# SCH_Iris_OnBoardSystem.net
KiCad netlist of a schematic drawn in EasyEDA
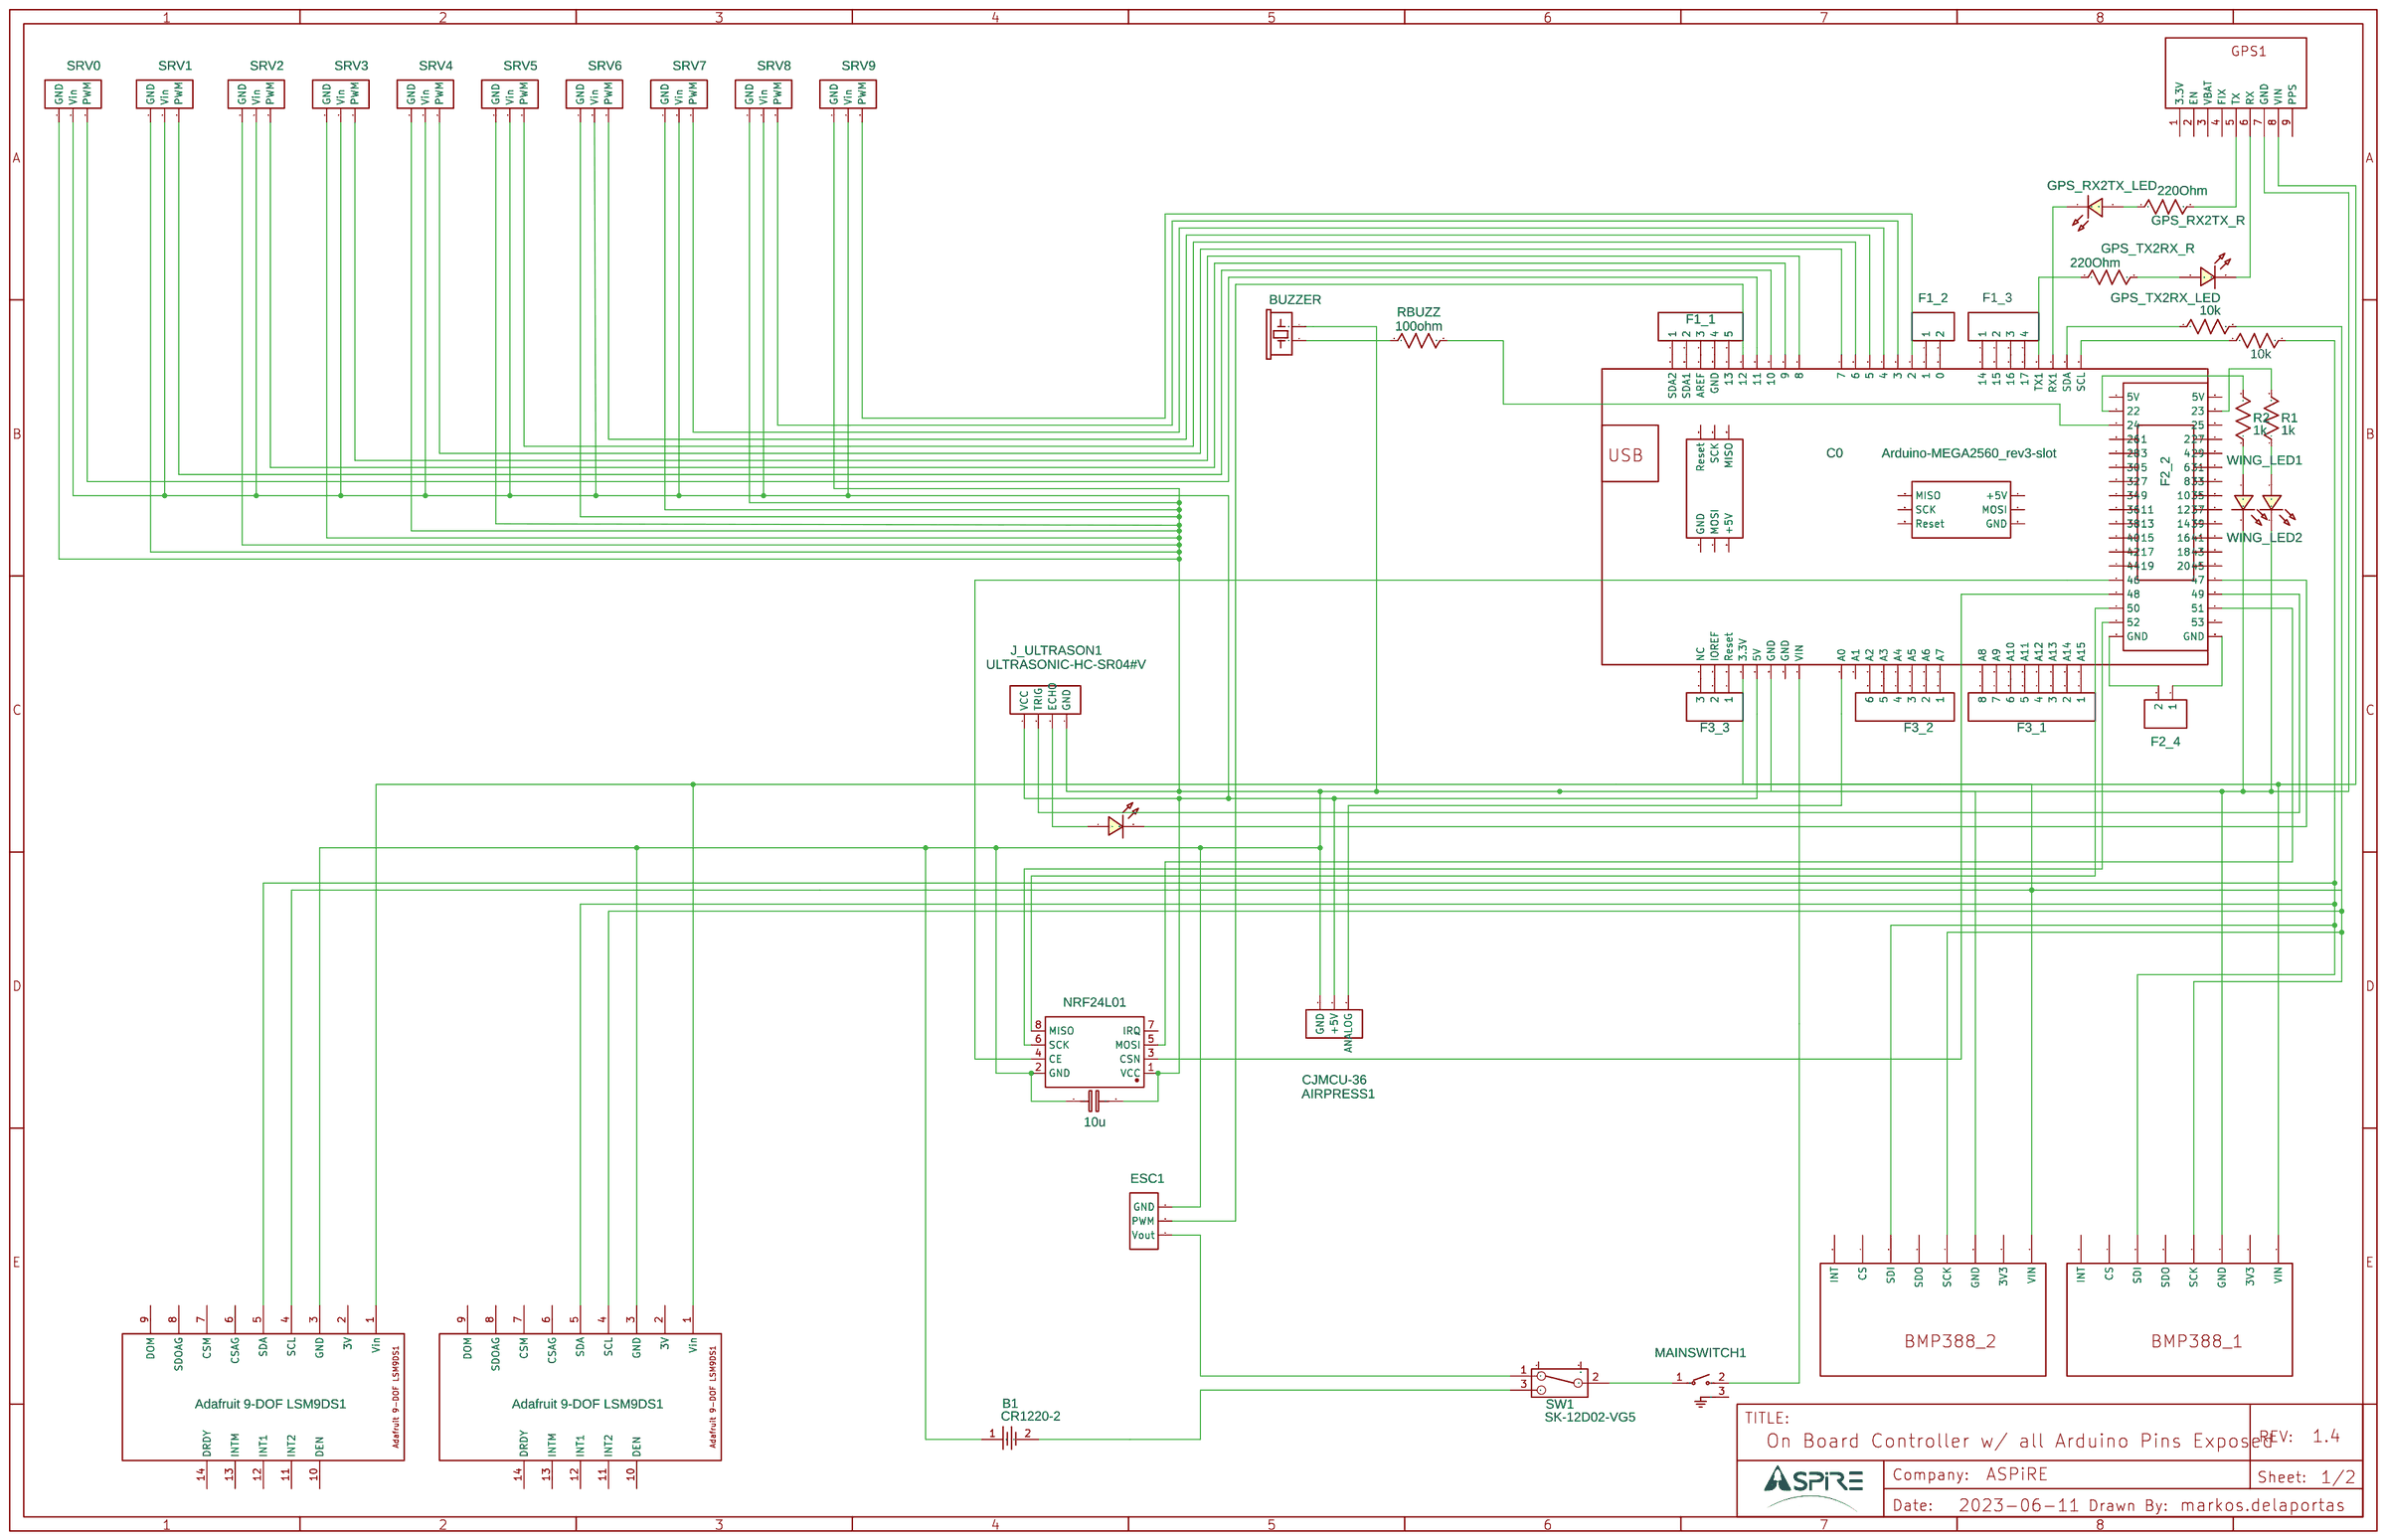
[diagram p0: schematic sheet]

(export (version "E")
  (design (tool "Eeschema 10.0.6"))
  (components
    (comp (ref "AIRPRESS1")
      (value "CJMCU-36")
      (fields (field (name "BOM_Supplier Part") "C180248"))
      (libsource (lib "") (part "HDR-M-2.54_1x3_1"))
    )
    (comp (ref "B1")
      (value "CR1220-2")
      (fields (field (name "BOM_Supplier Part") "C70381"))
      (libsource (lib "") (part "CR1220-2"))
    )
    (comp (ref "BUZZER") (value "BUZZER-PTH_NO_SILK") (libsource (lib "") (part "BUZZER-PTH_NO_SILK")))
    (comp (ref "C0")
      (value "Arduino-MEGA2560_rev3-slot")
      (libsource (lib "") (part "Arduino-MEGA2560_rev3-slot"))
    )
    (comp (ref "C1_2") (value "10u") (libsource (lib "") (part "C_RAD-0.1_EU")))
    (comp (ref "ESC1")
      (value "ESC")
      (fields (field (name "BOM_Supplier Part") "C180248"))
      (libsource (lib "") (part "HDR-M-2.54_1x3_2"))
    )
    (comp (ref "F1_1")
      (value "HDR-F-2.54_1x5")
      (fields (field (name "BOM_Supplier Part") "C50950"))
      (libsource (lib "") (part "HDR-F-2.54_1x5"))
    )
    (comp (ref "F1_2")
      (value "HDR-F-2.54_1x2")
      (fields (field (name "BOM_Supplier Part") "C49661"))
      (libsource (lib "") (part "HDR-F-2.54_1x2_1"))
    )
    (comp (ref "F1_3")
      (value "HDR-F-2.54_1x4")
      (fields (field (name "BOM_Supplier Part") "C225501"))
      (libsource (lib "") (part "HDR-F-2.54_1x4"))
    )
    (comp (ref "F2_2")
      (value "HDR-F-2.54_2x10")
      (fields (field (name "BOM_Supplier Part") "C30867"))
      (libsource (lib "") (part "HDR-F-2.54_2x10"))
    )
    (comp (ref "F2_4")
      (value "HDR-F-2.54_1x2")
      (fields (field (name "BOM_Supplier Part") "C49661"))
      (libsource (lib "") (part "HDR-F-2.54_1x2"))
    )
    (comp (ref "F3_1")
      (value "HDR-F-2.54_1x8")
      (fields (field (name "BOM_Supplier Part") "C225505"))
      (libsource (lib "") (part "HDR-F-2.54_1x8"))
    )
    (comp (ref "F3_2")
      (value "HDR-F-2.54_1x6")
      (fields (field (name "BOM_Supplier Part") "C40877"))
      (libsource (lib "") (part "HDR-F-2.54_1x6"))
    )
    (comp (ref "F3_3")
      (value "HDR-F-2.54_1x3")
      (fields (field (name "BOM_Supplier Part") "C146690"))
      (libsource (lib "") (part "HDR-F-2.54_1x3"))
    )
    (comp (ref "GPS2")
      (value "ULTIMATE GPS MODULE")
      (fields
        (field (name "BOM_Manufacturer Part") "Solid State Relays")
        (field (name "BOM_Supplier Part") "746")
      )
      (libsource (lib "") (part "ULTIMATE GPS MODULE"))
    )
    (comp (ref "GPS_RX2TX_LED")
      (value "LED-TH-5mm_R")
      (fields
        (field (name "BOM_Manufacturer Part") "333-2SURD/S530-A3")
        (field (name "BOM_Supplier Part") "C87271")
      )
      (libsource (lib "") (part "LED-TH-5mm_R"))
    )
    (comp (ref "GPS_RX2TX_R") (value "220Ohm") (libsource (lib "") (part "R_AXIAL-0.3_US_3")))
    (comp (ref "GPS_TX2RX_LED") (value "LED-TH-5mm_B") (libsource (lib "") (part "LED-TH-5mm_B")))
    (comp (ref "GPS_TX2RX_R") (value "220Ohm") (libsource (lib "") (part "R_AXIAL-0.3_US_1")))
    (comp (ref "J_ULTRASON1")
      (value "ULTRASONIC-HC-SR04#V")
      (fields (field (name "BOM_Supplier Part") "C124378"))
      (libsource (lib "") (part "HDR-M-2.54_1x4"))
    )
    (comp (ref "LED1_2")
      (value "LED-TH-3mm_R")
      (fields
        (field (name "BOM_Manufacturer Part") "204-10SDRD/S530-A3-L")
        (field (name "BOM_Supplier Part") "C84774")
      )
      (libsource (lib "") (part "LED-TH-3mm_R"))
    )
    (comp (ref "MAINSWITCH1")
      (value "GT-TCB73B-H090-L1")
      (fields (field (name "BOM_Supplier Part") "C2890355"))
      (libsource (lib "") (part "GT-TCB73B-H090-L1"))
    )
    (comp (ref "MK2")
      (value "NRF24L01")
      (fields (field (name "BOM_Manufacturer Part") "NF-04") (field (name "BOM_Supplier Part") "C90751"))
      (libsource (lib "") (part "NRF24L01"))
    )
    (comp (ref "R1") (value "1k") (libsource (lib "") (part "R_AXIAL-0.3_US")))
    (comp (ref "R1_2") (value "1k") (libsource (lib "") (part "R_AXIAL-0.4_US")))
    (comp (ref "R2") (value "1k") (libsource (lib "") (part "R_AXIAL-0.3_US")))
    (comp (ref "R2_2") (value "10k") (libsource (lib "") (part "R_AXIAL-0.4_US_1")))
    (comp (ref "RBUZZ") (value "100ohm") (libsource (lib "") (part "R_AXIAL-0.3_US_2")))
    (comp (ref "SRV0")
      (value "HDR-M-2.54_1x3")
      (fields (field (name "BOM_Supplier Part") "C180248"))
      (libsource (lib "") (part "HDR-M-2.54_1x3"))
    )
    (comp (ref "SRV1")
      (value "HDR-M-2.54_1x3")
      (fields (field (name "BOM_Supplier Part") "C180248"))
      (libsource (lib "") (part "HDR-M-2.54_1x3"))
    )
    (comp (ref "SRV2")
      (value "HDR-M-2.54_1x3")
      (fields (field (name "BOM_Supplier Part") "C180248"))
      (libsource (lib "") (part "HDR-M-2.54_1x3"))
    )
    (comp (ref "SRV3")
      (value "HDR-M-2.54_1x3")
      (fields (field (name "BOM_Supplier Part") "C180248"))
      (libsource (lib "") (part "HDR-M-2.54_1x3"))
    )
    (comp (ref "SRV4")
      (value "HDR-M-2.54_1x3")
      (fields (field (name "BOM_Supplier Part") "C180248"))
      (libsource (lib "") (part "HDR-M-2.54_1x3"))
    )
    (comp (ref "SRV5")
      (value "HDR-M-2.54_1x3")
      (fields (field (name "BOM_Supplier Part") "C180248"))
      (libsource (lib "") (part "HDR-M-2.54_1x3"))
    )
    (comp (ref "SRV6")
      (value "HDR-M-2.54_1x3")
      (fields (field (name "BOM_Supplier Part") "C180248"))
      (libsource (lib "") (part "HDR-M-2.54_1x3"))
    )
    (comp (ref "SRV7")
      (value "HDR-M-2.54_1x3")
      (fields (field (name "BOM_Supplier Part") "C180248"))
      (libsource (lib "") (part "HDR-M-2.54_1x3"))
    )
    (comp (ref "SRV8")
      (value "HDR-M-2.54_1x3")
      (fields (field (name "BOM_Supplier Part") "C180248"))
      (libsource (lib "") (part "HDR-M-2.54_1x3"))
    )
    (comp (ref "SRV9")
      (value "HDR-M-2.54_1x3")
      (fields (field (name "BOM_Supplier Part") "C180248"))
      (libsource (lib "") (part "HDR-M-2.54_1x3"))
    )
    (comp (ref "SW1")
      (value "SK-12D02-VG5")
      (fields (field (name "BOM_Supplier Part") "C136722"))
      (libsource (lib "") (part "SK-12D02-VG5"))
    )
    (comp (ref "U2")
      (value "Adafruit 9-DOF LSM9DS1")
      (fields (field (name "BOM_Manufacturer Part") "4634") (field (name "BOM_Supplier Part") "ADA4634"))
      (libsource (lib "") (part "Adafruit 9-DOF LSM9DS1"))
    )
    (comp (ref "U3")
      (value "Adafruit 9-DOF LSM9DS1")
      (fields (field (name "BOM_Manufacturer Part") "4634") (field (name "BOM_Supplier Part") "ADA4634"))
      (libsource (lib "") (part "Adafruit 9-DOF LSM9DS1"))
    )
    (comp (ref "U6")
      (value "ADAFRUIT_BMP388_2")
      (fields (field (name "BOM_Manufacturer Part") "BMP388") (field (name "BOM_Supplier Part") "3966"))
      (libsource (lib "") (part "ADAFRUIT BMP388 BOARD COPY"))
    )
    (comp (ref "U7")
      (value "ADAFRUIT_BMP388_1")
      (fields (field (name "BOM_Manufacturer Part") "BMP388") (field (name "BOM_Supplier Part") "3966"))
      (libsource (lib "") (part "ADAFRUIT BMP388 BOARD COPY_1"))
    )
    (comp (ref "WING_LED1")
      (value "LED-TH-5mm_G")
      (fields
        (field (name "BOM_Manufacturer Part") "333-2SYGD/S530-E2")
        (field (name "BOM_Supplier Part") "C88163")
      )
      (libsource (lib "") (part "LED-TH-5mm_G"))
    )
    (comp (ref "WING_LED2")
      (value "LED-TH-5mm_G")
      (fields
        (field (name "BOM_Manufacturer Part") "333-2SYGD/S530-E2")
        (field (name "BOM_Supplier Part") "C88163")
      )
      (libsource (lib "") (part "LED-TH-5mm_G"))
    )
  )
  (nets
    (net (code "1") (name "Net-(AIRPRESS1-+5V)") (class "Default")
      (node (ref "AIRPRESS1") (pin "2") (pinfunction "+5V_2") (pintype "input"))
      (node (ref "C0") (pin "5V") (pinfunction "5V_5V") (pintype "unspecified"))
      (node (ref "C1_2") (pin "2") (pinfunction "2_2") (pintype "unspecified"))
      (node (ref "J_ULTRASON1") (pin "1") (pinfunction "VCC_1") (pintype "unspecified"))
      (node (ref "MK2") (pin "1") (pinfunction "VCC_1") (pintype "unspecified"))
      (node (ref "SRV0") (pin "2") (pinfunction "Vin_2") (pintype "input"))
      (node (ref "SRV1") (pin "2") (pinfunction "Vin_2") (pintype "input"))
      (node (ref "SRV2") (pin "2") (pinfunction "Vin_2") (pintype "input"))
      (node (ref "SRV3") (pin "2") (pinfunction "Vin_2") (pintype "input"))
      (node (ref "SRV4") (pin "2") (pinfunction "Vin_2") (pintype "input"))
      (node (ref "SRV5") (pin "2") (pinfunction "Vin_2") (pintype "input"))
      (node (ref "SRV6") (pin "2") (pinfunction "Vin_2") (pintype "input"))
      (node (ref "SRV7") (pin "2") (pinfunction "Vin_2") (pintype "input"))
      (node (ref "SRV8") (pin "2") (pinfunction "Vin_2") (pintype "input"))
      (node (ref "SRV9") (pin "2") (pinfunction "Vin_2") (pintype "input"))
    )
    (net (code "2") (name "Net-(AIRPRESS1-ANALOG)") (class "Default")
      (node (ref "AIRPRESS1") (pin "1") (pinfunction "ANALOG_1") (pintype "input"))
      (node (ref "C0") (pin "A0") (pinfunction "A0_A0") (pintype "unspecified"))
    )
    (net (code "3") (name "Net-(AIRPRESS1-GND)") (class "Default")
      (node (ref "AIRPRESS1") (pin "3") (pinfunction "GND_3") (pintype "input"))
      (node (ref "B1") (pin "1") (pinfunction "1_1") (pintype "input"))
      (node (ref "BUZZER") (pin "-") (pinfunction "2_-") (pintype "bidirectional"))
      (node (ref "C1_2") (pin "1") (pinfunction "1_1") (pintype "unspecified"))
      (node (ref "ESC1") (pin "3") (pinfunction "GND_3") (pintype "input"))
      (node (ref "GPS2") (pin "7") (pinfunction "GND_7") (pintype "unspecified"))
      (node (ref "J_ULTRASON1") (pin "4") (pinfunction "GND_4") (pintype "unspecified"))
      (node (ref "MK2") (pin "2") (pinfunction "GND_2") (pintype "unspecified"))
      (node (ref "SRV0") (pin "1") (pinfunction "GND_1") (pintype "input"))
      (node (ref "SRV1") (pin "1") (pinfunction "GND_1") (pintype "input"))
      (node (ref "SRV2") (pin "1") (pinfunction "GND_1") (pintype "input"))
      (node (ref "SRV3") (pin "1") (pinfunction "GND_1") (pintype "input"))
      (node (ref "SRV4") (pin "1") (pinfunction "GND_1") (pintype "input"))
      (node (ref "SRV5") (pin "1") (pinfunction "GND_1") (pintype "input"))
      (node (ref "SRV6") (pin "1") (pinfunction "GND_1") (pintype "input"))
      (node (ref "SRV7") (pin "1") (pinfunction "GND_1") (pintype "input"))
      (node (ref "SRV8") (pin "1") (pinfunction "GND_1") (pintype "input"))
      (node (ref "SRV9") (pin "1") (pinfunction "GND_1") (pintype "input"))
      (node (ref "U2") (pin "3") (pinfunction "GND_3") (pintype "unspecified"))
      (node (ref "U3") (pin "3") (pinfunction "GND_3") (pintype "unspecified"))
      (node (ref "U7") (pin "3") (pinfunction "GND_3") (pintype "passive"))
      (node (ref "WING_LED1") (pin "2") (pinfunction "2_2") (pintype "unspecified"))
      (node (ref "WING_LED2") (pin "2") (pinfunction "2_2") (pintype "unspecified"))
    )
    (net (code "4") (name "Net-(B1-Pad2)") (class "Default")
      (node (ref "B1") (pin "2") (pinfunction "2_2") (pintype "input"))
      (node (ref "SW1") (pin "3") (pinfunction "3_3") (pintype "unspecified"))
    )
    (net (code "5") (name "Net-(BUZZER-1)") (class "Default")
      (node (ref "BUZZER") (pin "+") (pinfunction "1_+") (pintype "bidirectional"))
      (node (ref "RBUZZ") (pin "1") (pinfunction "1_1") (pintype "unspecified"))
    )
    (net (code "6") (name "Net-(C0-GND-PadGND...)") (class "Default")
      (node (ref "C0") (pin "GND...") (pinfunction "GND_GND...") (pintype "input"))
      (node (ref "F2_4") (pin "2") (pinfunction "2_2") (pintype "input"))
    )
    (net (code "7") (name "Net-(C0-GND-PadGND....)") (class "Default")
      (node (ref "C0") (pin "GND....") (pinfunction "GND_GND....") (pintype "input"))
      (node (ref "F2_4") (pin "1") (pinfunction "1_1") (pintype "input"))
    )
    (net (code "8") (name "Net-(C0-GND-PadGND.....)") (class "Default")
      (node (ref "C0") (pin "GND.....") (pinfunction "GND_GND.....") (pintype "unspecified"))
      (node (ref "F1_1") (pin "4") (pinfunction "4_4") (pintype "unspecified"))
    )
    (net (code "9") (name "Net-(C0-NC)") (class "Default")
      (node (ref "C0") (pin "87") (pinfunction "NC_87") (pintype "unspecified"))
      (node (ref "F3_3") (pin "3") (pinfunction "3_3") (pintype "input"))
    )
    (net (code "10") (name "Net-(C0-Pad0)") (class "Default")
      (node (ref "C0") (pin "0") (pinfunction "0_0") (pintype "unspecified"))
      (node (ref "F1_2") (pin "2") (pinfunction "2_2") (pintype "input"))
    )
    (net (code "11") (name "Net-(C0-Pad1)") (class "Default")
      (node (ref "C0") (pin "1") (pinfunction "1_1") (pintype "unspecified"))
      (node (ref "F1_2") (pin "1") (pinfunction "1_1") (pintype "input"))
    )
    (net (code "12") (name "Net-(C0-Pad13)") (class "Default")
      (node (ref "C0") (pin "13") (pinfunction "13_13") (pintype "unspecified"))
      (node (ref "F1_1") (pin "5") (pinfunction "5_5") (pintype "unspecified"))
    )
    (net (code "13") (name "Net-(C0-Pad14)") (class "Default")
      (node (ref "C0") (pin "14") (pinfunction "14_14") (pintype "unspecified"))
      (node (ref "F1_3") (pin "1") (pinfunction "1_1") (pintype "unspecified"))
    )
    (net (code "14") (name "Net-(C0-Pad15)") (class "Default")
      (node (ref "C0") (pin "15") (pinfunction "15_15") (pintype "unspecified"))
      (node (ref "F1_3") (pin "2") (pinfunction "2_2") (pintype "unspecified"))
    )
    (net (code "15") (name "Net-(C0-Pad16)") (class "Default")
      (node (ref "C0") (pin "16") (pinfunction "16_16") (pintype "unspecified"))
      (node (ref "F1_3") (pin "3") (pinfunction "3_3") (pintype "unspecified"))
    )
    (net (code "16") (name "Net-(C0-Pad17)") (class "Default")
      (node (ref "C0") (pin "17") (pinfunction "17_17") (pintype "unspecified"))
      (node (ref "F1_3") (pin "4") (pinfunction "4_4") (pintype "unspecified"))
    )
    (net (code "17") (name "Net-(C0-Pad22)") (class "Default")
      (node (ref "C0") (pin "22") (pinfunction "22_22") (pintype "input"))
      (node (ref "R2") (pin "2") (pinfunction "2_2") (pintype "unspecified"))
    )
    (net (code "18") (name "Net-(C0-Pad23)") (class "Default")
      (node (ref "C0") (pin "23") (pinfunction "23_23") (pintype "input"))
      (node (ref "R1") (pin "2") (pinfunction "2_2") (pintype "unspecified"))
    )
    (net (code "19") (name "Net-(C0-Pad24)") (class "Default")
      (node (ref "C0") (pin "24") (pinfunction "24_24") (pintype "input"))
      (node (ref "RBUZZ") (pin "2") (pinfunction "2_2") (pintype "unspecified"))
    )
    (net (code "20") (name "Net-(C0-Pad26)") (class "Default")
      (node (ref "C0") (pin "26") (pinfunction "26_26") (pintype "input"))
      (node (ref "F2_2") (pin "1") (pinfunction "1_1") (pintype "input"))
    )
    (net (code "21") (name "Net-(C0-Pad27)") (class "Default")
      (node (ref "C0") (pin "27") (pinfunction "27_27") (pintype "input"))
      (node (ref "F2_2") (pin "2") (pinfunction "2_2") (pintype "input"))
    )
    (net (code "22") (name "Net-(C0-Pad28)") (class "Default")
      (node (ref "C0") (pin "28") (pinfunction "28_28") (pintype "input"))
      (node (ref "F2_2") (pin "3") (pinfunction "3_3") (pintype "input"))
    )
    (net (code "23") (name "Net-(C0-Pad29)") (class "Default")
      (node (ref "C0") (pin "29") (pinfunction "29_29") (pintype "input"))
      (node (ref "F2_2") (pin "4") (pinfunction "4_4") (pintype "input"))
    )
    (net (code "24") (name "Net-(C0-Pad30)") (class "Default")
      (node (ref "C0") (pin "30") (pinfunction "30_30") (pintype "input"))
      (node (ref "F2_2") (pin "5") (pinfunction "5_5") (pintype "input"))
    )
    (net (code "25") (name "Net-(C0-Pad31)") (class "Default")
      (node (ref "C0") (pin "31") (pinfunction "31_31") (pintype "input"))
      (node (ref "F2_2") (pin "6") (pinfunction "6_6") (pintype "input"))
    )
    (net (code "26") (name "Net-(C0-Pad32)") (class "Default")
      (node (ref "C0") (pin "32") (pinfunction "32_32") (pintype "input"))
      (node (ref "F2_2") (pin "7") (pinfunction "7_7") (pintype "input"))
    )
    (net (code "27") (name "Net-(C0-Pad33)") (class "Default")
      (node (ref "C0") (pin "33") (pinfunction "33_33") (pintype "input"))
      (node (ref "F2_2") (pin "8") (pinfunction "8_8") (pintype "input"))
    )
    (net (code "28") (name "Net-(C0-Pad34)") (class "Default")
      (node (ref "C0") (pin "34") (pinfunction "34_34") (pintype "input"))
      (node (ref "F2_2") (pin "9") (pinfunction "9_9") (pintype "input"))
    )
    (net (code "29") (name "Net-(C0-Pad35)") (class "Default")
      (node (ref "C0") (pin "35") (pinfunction "35_35") (pintype "input"))
      (node (ref "F2_2") (pin "10") (pinfunction "10_10") (pintype "input"))
    )
    (net (code "30") (name "Net-(C0-Pad36)") (class "Default")
      (node (ref "C0") (pin "36") (pinfunction "36_36") (pintype "input"))
      (node (ref "F2_2") (pin "11") (pinfunction "11_11") (pintype "input"))
    )
    (net (code "31") (name "Net-(C0-Pad37)") (class "Default")
      (node (ref "C0") (pin "37") (pinfunction "37_37") (pintype "input"))
      (node (ref "F2_2") (pin "12") (pinfunction "12_12") (pintype "input"))
    )
    (net (code "32") (name "Net-(C0-Pad38)") (class "Default")
      (node (ref "C0") (pin "38") (pinfunction "38_38") (pintype "input"))
      (node (ref "F2_2") (pin "13") (pinfunction "13_13") (pintype "input"))
    )
    (net (code "33") (name "Net-(C0-Pad39)") (class "Default")
      (node (ref "C0") (pin "39") (pinfunction "39_39") (pintype "input"))
      (node (ref "F2_2") (pin "14") (pinfunction "14_14") (pintype "input"))
    )
    (net (code "34") (name "Net-(C0-Pad40)") (class "Default")
      (node (ref "C0") (pin "40") (pinfunction "40_40") (pintype "input"))
      (node (ref "F2_2") (pin "15") (pinfunction "15_15") (pintype "input"))
    )
    (net (code "35") (name "Net-(C0-Pad41)") (class "Default")
      (node (ref "C0") (pin "41") (pinfunction "41_41") (pintype "input"))
      (node (ref "F2_2") (pin "16") (pinfunction "16_16") (pintype "input"))
    )
    (net (code "36") (name "Net-(C0-Pad42)") (class "Default")
      (node (ref "C0") (pin "42") (pinfunction "42_42") (pintype "input"))
      (node (ref "F2_2") (pin "17") (pinfunction "17_17") (pintype "input"))
    )
    (net (code "37") (name "Net-(C0-Pad43)") (class "Default")
      (node (ref "C0") (pin "43") (pinfunction "43_43") (pintype "input"))
      (node (ref "F2_2") (pin "18") (pinfunction "18_18") (pintype "input"))
    )
    (net (code "38") (name "Net-(C0-Pad44)") (class "Default")
      (node (ref "C0") (pin "44") (pinfunction "44_44") (pintype "input"))
      (node (ref "F2_2") (pin "19") (pinfunction "19_19") (pintype "input"))
    )
    (net (code "39") (name "Net-(C0-Pad45)") (class "Default")
      (node (ref "C0") (pin "45") (pinfunction "45_45") (pintype "input"))
      (node (ref "F2_2") (pin "20") (pinfunction "20_20") (pintype "input"))
    )
    (net (code "40") (name "Net-(C0-Pad47)") (class "Default")
      (node (ref "C0") (pin "47") (pinfunction "47_47") (pintype "input"))
      (node (ref "LED1_2") (pin "2") (pinfunction "2_2") (pintype "unspecified"))
    )
    (net (code "41") (name "Net-(C0-PadA2)") (class "Default")
      (node (ref "C0") (pin "A2") (pinfunction "A2_A2") (pintype "unspecified"))
      (node (ref "F3_2") (pin "6") (pinfunction "6_6") (pintype "input"))
    )
    (net (code "42") (name "Net-(C0-PadA3)") (class "Default")
      (node (ref "C0") (pin "A3") (pinfunction "A3_A3") (pintype "unspecified"))
      (node (ref "F3_2") (pin "5") (pinfunction "5_5") (pintype "input"))
    )
    (net (code "43") (name "Net-(C0-PadA4)") (class "Default")
      (node (ref "C0") (pin "A4") (pinfunction "A4_A4") (pintype "unspecified"))
      (node (ref "F3_2") (pin "4") (pinfunction "4_4") (pintype "input"))
    )
    (net (code "44") (name "Net-(C0-PadA5)") (class "Default")
      (node (ref "C0") (pin "A5") (pinfunction "A5_A5") (pintype "unspecified"))
      (node (ref "F3_2") (pin "3") (pinfunction "3_3") (pintype "input"))
    )
    (net (code "45") (name "Net-(C0-PadA6)") (class "Default")
      (node (ref "C0") (pin "A6") (pinfunction "A6_A6") (pintype "unspecified"))
      (node (ref "F3_2") (pin "2") (pinfunction "2_2") (pintype "input"))
    )
    (net (code "46") (name "Net-(C0-PadA7)") (class "Default")
      (node (ref "C0") (pin "A7") (pinfunction "A7_A7") (pintype "unspecified"))
      (node (ref "F3_2") (pin "1") (pinfunction "1_1") (pintype "input"))
    )
    (net (code "47") (name "Net-(C0-PadA8)") (class "Default")
      (node (ref "C0") (pin "A8") (pinfunction "A8_A8") (pintype "unspecified"))
      (node (ref "F3_1") (pin "8") (pinfunction "8_8") (pintype "unspecified"))
    )
    (net (code "48") (name "Net-(C0-PadA9)") (class "Default")
      (node (ref "C0") (pin "A9") (pinfunction "A9_A9") (pintype "unspecified"))
      (node (ref "F3_1") (pin "7") (pinfunction "7_7") (pintype "unspecified"))
    )
    (net (code "49") (name "Net-(C0-PadA10)") (class "Default")
      (node (ref "C0") (pin "A10") (pinfunction "A10_A10") (pintype "unspecified"))
      (node (ref "F3_1") (pin "6") (pinfunction "6_6") (pintype "unspecified"))
    )
    (net (code "50") (name "Net-(C0-PadA11)") (class "Default")
      (node (ref "C0") (pin "A11") (pinfunction "A11_A11") (pintype "unspecified"))
      (node (ref "F3_1") (pin "5") (pinfunction "5_5") (pintype "unspecified"))
    )
    (net (code "51") (name "Net-(C0-PadA12)") (class "Default")
      (node (ref "C0") (pin "A12") (pinfunction "A12_A12") (pintype "unspecified"))
      (node (ref "F3_1") (pin "4") (pinfunction "4_4") (pintype "unspecified"))
    )
    (net (code "52") (name "Net-(C0-PadA13)") (class "Default")
      (node (ref "C0") (pin "A13") (pinfunction "A13_A13") (pintype "unspecified"))
      (node (ref "F3_1") (pin "3") (pinfunction "3_3") (pintype "unspecified"))
    )
    (net (code "53") (name "Net-(C0-PadA14)") (class "Default")
      (node (ref "C0") (pin "A14") (pinfunction "A14_A14") (pintype "unspecified"))
      (node (ref "F3_1") (pin "2") (pinfunction "2_2") (pintype "unspecified"))
    )
    (net (code "54") (name "Net-(C0-PadA15)") (class "Default")
      (node (ref "C0") (pin "A15") (pinfunction "A15_A15") (pintype "unspecified"))
      (node (ref "F3_1") (pin "1") (pinfunction "1_1") (pintype "unspecified"))
    )
    (net (code "55") (name "Net-(C0-PadAREF)") (class "Default")
      (node (ref "C0") (pin "AREF") (pinfunction "AREF_AREF") (pintype "unspecified"))
      (node (ref "F1_1") (pin "3") (pinfunction "3_3") (pintype "unspecified"))
    )
    (net (code "56") (name "Net-(C0-PadIOREF)") (class "Default")
      (node (ref "C0") (pin "IOREF") (pinfunction "IOREF_IOREF") (pintype "unspecified"))
      (node (ref "F3_3") (pin "2") (pinfunction "2_2") (pintype "input"))
    )
    (net (code "57") (name "Net-(C0-PadSDA1)") (class "Default")
      (node (ref "C0") (pin "SDA1") (pinfunction "SDA1_SDA1") (pintype "unspecified"))
      (node (ref "F1_1") (pin "2") (pinfunction "2_2") (pintype "unspecified"))
    )
    (net (code "58") (name "Net-(C0-PadSDA2)") (class "Default")
      (node (ref "C0") (pin "SDA2") (pinfunction "SDA2_SDA2") (pintype "unspecified"))
      (node (ref "F1_1") (pin "1") (pinfunction "1_1") (pintype "unspecified"))
    )
    (net (code "59") (name "Net-(C0-PadVIN)") (class "Default")
      (node (ref "C0") (pin "VIN") (pinfunction "VIN_VIN") (pintype "unspecified"))
      (node (ref "MAINSWITCH1") (pin "2") (pinfunction "2_2") (pintype "unspecified"))
    )
    (net (code "60") (name "Net-(C0-RX1)") (class "Default")
      (node (ref "C0") (pin "19") (pinfunction "RX1_19") (pintype "unspecified"))
      (node (ref "GPS_RX2TX_LED") (pin "2") (pinfunction "2_2") (pintype "unspecified"))
    )
    (net (code "61") (name "Net-(C0-Reset-PadRST)") (class "Default")
      (node (ref "C0") (pin "RST") (pinfunction "Reset_RST") (pintype "unspecified"))
      (node (ref "F3_3") (pin "1") (pinfunction "1_1") (pintype "input"))
    )
    (net (code "62") (name "Net-(C0-SCL)") (class "Default")
      (node (ref "C0") (pin "21") (pinfunction "SCL_21") (pintype "unspecified"))
      (node (ref "R1_2") (pin "1") (pinfunction "1_1") (pintype "unspecified"))
    )
    (net (code "63") (name "Net-(C0-SDA)") (class "Default")
      (node (ref "C0") (pin "20") (pinfunction "SDA_20") (pintype "unspecified"))
      (node (ref "R2_2") (pin "1") (pinfunction "1_1") (pintype "unspecified"))
    )
    (net (code "64") (name "Net-(C0-TX1)") (class "Default")
      (node (ref "C0") (pin "18") (pinfunction "TX1_18") (pintype "unspecified"))
      (node (ref "GPS_TX2RX_R") (pin "1") (pinfunction "1_1") (pintype "unspecified"))
    )
    (net (code "65") (name "Net-(ESC1-PWM)") (class "Default")
      (node (ref "C0") (pin "12") (pinfunction "12_12") (pintype "unspecified"))
      (node (ref "ESC1") (pin "2") (pinfunction "PWM_2") (pintype "input"))
    )
    (net (code "66") (name "Net-(ESC1-Vout)") (class "Default")
      (node (ref "ESC1") (pin "1") (pinfunction "Vout_1") (pintype "input"))
      (node (ref "SW1") (pin "1") (pinfunction "1_1") (pintype "unspecified"))
    )
    (net (code "67") (name "Net-(GPS2-RX)") (class "Default")
      (node (ref "GPS2") (pin "6") (pinfunction "RX_6") (pintype "unspecified"))
      (node (ref "GPS_TX2RX_LED") (pin "2") (pinfunction "2_2") (pintype "unspecified"))
    )
    (net (code "68") (name "Net-(GPS2-TX)") (class "Default")
      (node (ref "GPS2") (pin "5") (pinfunction "TX_5") (pintype "unspecified"))
      (node (ref "GPS_RX2TX_R") (pin "2") (pinfunction "2_2") (pintype "unspecified"))
    )
    (net (code "69") (name "Net-(GPS2-VIN)") (class "Default")
      (node (ref "GPS2") (pin "8") (pinfunction "VIN_8") (pintype "unspecified"))
      (node (ref "U2") (pin "1") (pinfunction "Vin_1") (pintype "unspecified"))
      (node (ref "U3") (pin "1") (pinfunction "Vin_1") (pintype "unspecified"))
      (node (ref "U7") (pin "1") (pinfunction "VIN_1") (pintype "passive"))
    )
    (net (code "70") (name "Net-(GPS_RX2TX_LED-Pad1)") (class "Default")
      (node (ref "GPS_RX2TX_LED") (pin "1") (pinfunction "1_1") (pintype "unspecified"))
      (node (ref "GPS_RX2TX_R") (pin "1") (pinfunction "1_1") (pintype "unspecified"))
    )
    (net (code "71") (name "Net-(GPS_TX2RX_LED-Pad1)") (class "Default")
      (node (ref "GPS_TX2RX_LED") (pin "1") (pinfunction "1_1") (pintype "unspecified"))
      (node (ref "GPS_TX2RX_R") (pin "2") (pinfunction "2_2") (pintype "unspecified"))
    )
    (net (code "72") (name "Net-(J_ULTRASON1-ECHO)") (class "Default")
      (node (ref "J_ULTRASON1") (pin "3") (pinfunction "ECHO_3") (pintype "unspecified"))
      (node (ref "LED1_2") (pin "1") (pinfunction "1_1") (pintype "unspecified"))
    )
    (net (code "73") (name "Net-(J_ULTRASON1-TRIG)") (class "Default")
      (node (ref "C0") (pin "49") (pinfunction "49_49") (pintype "input"))
      (node (ref "J_ULTRASON1") (pin "2") (pinfunction "TRIG_2") (pintype "unspecified"))
    )
    (net (code "74") (name "Net-(MAINSWITCH1-Pad1)") (class "Default")
      (node (ref "MAINSWITCH1") (pin "1") (pinfunction "1_1") (pintype "unspecified"))
      (node (ref "SW1") (pin "2") (pinfunction "2_2") (pintype "unspecified"))
    )
    (net (code "75") (name "Net-(MK2-CE)") (class "Default")
      (node (ref "C0") (pin "46") (pinfunction "46_46") (pintype "input"))
      (node (ref "MK2") (pin "4") (pinfunction "CE_4") (pintype "unspecified"))
    )
    (net (code "76") (name "Net-(MK2-CSN)") (class "Default")
      (node (ref "C0") (pin "48") (pinfunction "48_48") (pintype "input"))
      (node (ref "MK2") (pin "3") (pinfunction "CSN_3") (pintype "unspecified"))
    )
    (net (code "77") (name "Net-(MK2-MISO)") (class "Default")
      (node (ref "C0") (pin "50") (pinfunction "50_50") (pintype "input"))
      (node (ref "MK2") (pin "8") (pinfunction "MISO_8") (pintype "unspecified"))
    )
    (net (code "78") (name "Net-(MK2-MOSI)") (class "Default")
      (node (ref "C0") (pin "51") (pinfunction "51_51") (pintype "input"))
      (node (ref "MK2") (pin "5") (pinfunction "MOSI_5") (pintype "unspecified"))
    )
    (net (code "79") (name "Net-(MK2-SCK)") (class "Default")
      (node (ref "C0") (pin "52") (pinfunction "52_52") (pintype "input"))
      (node (ref "MK2") (pin "6") (pinfunction "SCK_6") (pintype "unspecified"))
    )
    (net (code "80") (name "Net-(R1-Pad1)") (class "Default")
      (node (ref "R1") (pin "1") (pinfunction "1_1") (pintype "unspecified"))
      (node (ref "WING_LED1") (pin "1") (pinfunction "1_1") (pintype "unspecified"))
    )
    (net (code "81") (name "Net-(R2-Pad1)") (class "Default")
      (node (ref "R2") (pin "1") (pinfunction "1_1") (pintype "unspecified"))
      (node (ref "WING_LED2") (pin "1") (pinfunction "1_1") (pintype "unspecified"))
    )
    (net (code "82") (name "Net-(SRV0-PWM)") (class "Default")
      (node (ref "C0") (pin "11") (pinfunction "11_11") (pintype "unspecified"))
      (node (ref "SRV0") (pin "3") (pinfunction "PWM_3") (pintype "input"))
    )
    (net (code "83") (name "Net-(SRV1-PWM)") (class "Default")
      (node (ref "C0") (pin "10") (pinfunction "10_10") (pintype "unspecified"))
      (node (ref "SRV1") (pin "3") (pinfunction "PWM_3") (pintype "input"))
    )
    (net (code "84") (name "Net-(SRV2-PWM)") (class "Default")
      (node (ref "C0") (pin "9") (pinfunction "9_9") (pintype "unspecified"))
      (node (ref "SRV2") (pin "3") (pinfunction "PWM_3") (pintype "input"))
    )
    (net (code "85") (name "Net-(SRV3-PWM)") (class "Default")
      (node (ref "C0") (pin "8") (pinfunction "8_8") (pintype "unspecified"))
      (node (ref "SRV3") (pin "3") (pinfunction "PWM_3") (pintype "input"))
    )
    (net (code "86") (name "Net-(SRV4-PWM)") (class "Default")
      (node (ref "C0") (pin "7") (pinfunction "7_7") (pintype "unspecified"))
      (node (ref "SRV4") (pin "3") (pinfunction "PWM_3") (pintype "input"))
    )
    (net (code "87") (name "Net-(SRV5-PWM)") (class "Default")
      (node (ref "C0") (pin "6") (pinfunction "6_6") (pintype "unspecified"))
      (node (ref "SRV5") (pin "3") (pinfunction "PWM_3") (pintype "input"))
    )
    (net (code "88") (name "Net-(SRV6-PWM)") (class "Default")
      (node (ref "C0") (pin "5") (pinfunction "5_5") (pintype "unspecified"))
      (node (ref "SRV6") (pin "3") (pinfunction "PWM_3") (pintype "input"))
    )
    (net (code "89") (name "Net-(SRV7-PWM)") (class "Default")
      (node (ref "C0") (pin "4") (pinfunction "4_4") (pintype "unspecified"))
      (node (ref "SRV7") (pin "3") (pinfunction "PWM_3") (pintype "input"))
    )
    (net (code "90") (name "Net-(SRV8-PWM)") (class "Default")
      (node (ref "C0") (pin "3") (pinfunction "3_3") (pintype "unspecified"))
      (node (ref "SRV8") (pin "3") (pinfunction "PWM_3") (pintype "input"))
    )
    (net (code "91") (name "Net-(SRV9-PWM)") (class "Default")
      (node (ref "C0") (pin "2") (pinfunction "2_2") (pintype "unspecified"))
      (node (ref "SRV9") (pin "3") (pinfunction "PWM_3") (pintype "input"))
    )
    (net (code "92") (name "Net-(U2-SCL)") (class "Default")
      (node (ref "C0") (pin "3.3V") (pinfunction "3.3V_3.3V") (pintype "unspecified"))
      (node (ref "R2_2") (pin "2") (pinfunction "2_2") (pintype "unspecified"))
      (node (ref "U2") (pin "4") (pinfunction "SCL_4") (pintype "unspecified"))
      (node (ref "U3") (pin "4") (pinfunction "SCL_4") (pintype "unspecified"))
      (node (ref "U6") (pin "1") (pinfunction "VIN_1") (pintype "passive"))
      (node (ref "U6") (pin "4") (pinfunction "SCK_4") (pintype "input"))
      (node (ref "U7") (pin "4") (pinfunction "SCK_4") (pintype "input"))
    )
    (net (code "93") (name "Net-(U2-SDA)") (class "Default")
      (node (ref "R1_2") (pin "2") (pinfunction "2_2") (pintype "unspecified"))
      (node (ref "U2") (pin "5") (pinfunction "SDA_5") (pintype "unspecified"))
      (node (ref "U3") (pin "5") (pinfunction "SDA_5") (pintype "unspecified"))
      (node (ref "U6") (pin "6") (pinfunction "SDI_6") (pintype "bidirectional"))
      (node (ref "U7") (pin "6") (pinfunction "SDI_6") (pintype "bidirectional"))
    )
    (net (code "94") (name "Net-(U6-GND)") (class "Default")
      (node (ref "C0") (pin "GND..") (pinfunction "GND_GND..") (pintype "unspecified"))
      (node (ref "U6") (pin "3") (pinfunction "GND_3") (pintype "passive"))
    )
    (net (code "95") (name "unconnected-(C0-+5V-Pad+5V_)") (class "Default")
      (node (ref "C0") (pin "+5V_") (pinfunction "+5V_+5V_") (pintype "input"))
    )
    (net (code "96") (name "unconnected-(C0-+5V-Pad+5V_2)") (class "Default")
      (node (ref "C0") (pin "+5V_2") (pinfunction "+5V_+5V_2") (pintype "input"))
    )
    (net (code "97") (name "unconnected-(C0-5V-Pad5V.)") (class "Default")
      (node (ref "C0") (pin "5V.") (pinfunction "5V_5V.") (pintype "input"))
    )
    (net (code "98") (name "unconnected-(C0-5V-Pad5V..)") (class "Default")
      (node (ref "C0") (pin "5V..") (pinfunction "5V_5V..") (pintype "input"))
    )
    (net (code "99") (name "unconnected-(C0-GND-PadGND.)") (class "Default")
      (node (ref "C0") (pin "GND.") (pinfunction "GND_GND.") (pintype "unspecified"))
    )
    (net (code "100") (name "unconnected-(C0-GND-PadGND_)") (class "Default")
      (node (ref "C0") (pin "GND_") (pinfunction "GND_GND_") (pintype "input"))
    )
    (net (code "101") (name "unconnected-(C0-GND-PadGND_2)") (class "Default")
      (node (ref "C0") (pin "GND_2") (pinfunction "GND_GND_2") (pintype "input"))
    )
    (net (code "102") (name "unconnected-(C0-MISO-PadMISO2)") (class "Default")
      (node (ref "C0") (pin "MISO2") (pinfunction "MISO_MISO2") (pintype "input"))
    )
    (net (code "103") (name "unconnected-(C0-MOSI-PadMOSI2)") (class "Default")
      (node (ref "C0") (pin "MOSI2") (pinfunction "MOSI_MOSI2") (pintype "input"))
    )
    (net (code "104") (name "unconnected-(C0-Pad25)") (class "Default")
      (node (ref "C0") (pin "25") (pinfunction "25_25") (pintype "input"))
    )
    (net (code "105") (name "unconnected-(C0-Pad53)") (class "Default")
      (node (ref "C0") (pin "53") (pinfunction "53_53") (pintype "input"))
    )
    (net (code "106") (name "unconnected-(C0-PadA1)") (class "Default")
      (node (ref "C0") (pin "A1") (pinfunction "A1_A1") (pintype "unspecified"))
    )
    (net (code "107") (name "unconnected-(C0-PadMISO)") (class "Default")
      (node (ref "C0") (pin "MISO") (pinfunction "MISO_MISO") (pintype "input"))
    )
    (net (code "108") (name "unconnected-(C0-PadMOSI)") (class "Default")
      (node (ref "C0") (pin "MOSI") (pinfunction "MOSI_MOSI") (pintype "input"))
    )
    (net (code "109") (name "unconnected-(C0-PadSCK)") (class "Default")
      (node (ref "C0") (pin "SCK") (pinfunction "SCK_SCK") (pintype "input"))
    )
    (net (code "110") (name "unconnected-(C0-Reset-PadRESET2)") (class "Default")
      (node (ref "C0") (pin "RESET2") (pinfunction "Reset_RESET2") (pintype "input"))
    )
    (net (code "111") (name "unconnected-(C0-Reset-PadRESET_)") (class "Default")
      (node (ref "C0") (pin "RESET_") (pinfunction "Reset_RESET_") (pintype "input"))
    )
    (net (code "112") (name "unconnected-(C0-SCK-PadSCK2)") (class "Default")
      (node (ref "C0") (pin "SCK2") (pinfunction "SCK_SCK2") (pintype "input"))
    )
    (net (code "113") (name "unconnected-(GPS2-3.3V-Pad1)") (class "Default")
      (node (ref "GPS2") (pin "1") (pinfunction "3.3V_1") (pintype "unspecified"))
    )
    (net (code "114") (name "unconnected-(GPS2-EN-Pad2)") (class "Default")
      (node (ref "GPS2") (pin "2") (pinfunction "EN_2") (pintype "unspecified"))
    )
    (net (code "115") (name "unconnected-(GPS2-FIX-Pad4)") (class "Default")
      (node (ref "GPS2") (pin "4") (pinfunction "FIX_4") (pintype "unspecified"))
    )
    (net (code "116") (name "unconnected-(GPS2-PPS-Pad9)") (class "Default")
      (node (ref "GPS2") (pin "9") (pinfunction "PPS_9") (pintype "unspecified"))
    )
    (net (code "117") (name "unconnected-(GPS2-VBAT-Pad3)") (class "Default")
      (node (ref "GPS2") (pin "3") (pinfunction "VBAT_3") (pintype "unspecified"))
    )
    (net (code "118") (name "unconnected-(MAINSWITCH1-Pad3)") (class "Default")
      (node (ref "MAINSWITCH1") (pin "3") (pinfunction "3_3") (pintype "unspecified"))
    )
    (net (code "119") (name "unconnected-(MK2-IRQ-Pad7)") (class "Default")
      (node (ref "MK2") (pin "7") (pinfunction "IRQ_7") (pintype "unspecified"))
    )
    (net (code "120") (name "unconnected-(SW1-Pad4)") (class "Default")
      (node (ref "SW1") (pin "4") (pinfunction "4_4") (pintype "unspecified"))
    )
    (net (code "121") (name "unconnected-(SW1-Pad5)") (class "Default")
      (node (ref "SW1") (pin "5") (pinfunction "5_5") (pintype "unspecified"))
    )
    (net (code "122") (name "unconnected-(U2-3V-Pad2)") (class "Default")
      (node (ref "U2") (pin "2") (pinfunction "3V_2") (pintype "unspecified"))
    )
    (net (code "123") (name "unconnected-(U2-CSAG-Pad6)") (class "Default")
      (node (ref "U2") (pin "6") (pinfunction "CSAG_6") (pintype "unspecified"))
    )
    (net (code "124") (name "unconnected-(U2-CSM-Pad7)") (class "Default")
      (node (ref "U2") (pin "7") (pinfunction "CSM_7") (pintype "unspecified"))
    )
    (net (code "125") (name "unconnected-(U2-DEN-Pad10)") (class "Default")
      (node (ref "U2") (pin "10") (pinfunction "DEN_10") (pintype "unspecified"))
    )
    (net (code "126") (name "unconnected-(U2-DOM-Pad9)") (class "Default")
      (node (ref "U2") (pin "9") (pinfunction "DOM_9") (pintype "unspecified"))
    )
    (net (code "127") (name "unconnected-(U2-DRDY-Pad14)") (class "Default")
      (node (ref "U2") (pin "14") (pinfunction "DRDY_14") (pintype "unspecified"))
    )
    (net (code "128") (name "unconnected-(U2-INT1-Pad12)") (class "Default")
      (node (ref "U2") (pin "12") (pinfunction "INT1_12") (pintype "unspecified"))
    )
    (net (code "129") (name "unconnected-(U2-INT2-Pad11)") (class "Default")
      (node (ref "U2") (pin "11") (pinfunction "INT2_11") (pintype "unspecified"))
    )
    (net (code "130") (name "unconnected-(U2-INTM-Pad13)") (class "Default")
      (node (ref "U2") (pin "13") (pinfunction "INTM_13") (pintype "unspecified"))
    )
    (net (code "131") (name "unconnected-(U2-SDOAG-Pad8)") (class "Default")
      (node (ref "U2") (pin "8") (pinfunction "SDOAG_8") (pintype "unspecified"))
    )
    (net (code "132") (name "unconnected-(U3-3V-Pad2)") (class "Default")
      (node (ref "U3") (pin "2") (pinfunction "3V_2") (pintype "unspecified"))
    )
    (net (code "133") (name "unconnected-(U3-CSAG-Pad6)") (class "Default")
      (node (ref "U3") (pin "6") (pinfunction "CSAG_6") (pintype "unspecified"))
    )
    (net (code "134") (name "unconnected-(U3-CSM-Pad7)") (class "Default")
      (node (ref "U3") (pin "7") (pinfunction "CSM_7") (pintype "unspecified"))
    )
    (net (code "135") (name "unconnected-(U3-DEN-Pad10)") (class "Default")
      (node (ref "U3") (pin "10") (pinfunction "DEN_10") (pintype "unspecified"))
    )
    (net (code "136") (name "unconnected-(U3-DOM-Pad9)") (class "Default")
      (node (ref "U3") (pin "9") (pinfunction "DOM_9") (pintype "unspecified"))
    )
    (net (code "137") (name "unconnected-(U3-DRDY-Pad14)") (class "Default")
      (node (ref "U3") (pin "14") (pinfunction "DRDY_14") (pintype "unspecified"))
    )
    (net (code "138") (name "unconnected-(U3-INT1-Pad12)") (class "Default")
      (node (ref "U3") (pin "12") (pinfunction "INT1_12") (pintype "unspecified"))
    )
    (net (code "139") (name "unconnected-(U3-INT2-Pad11)") (class "Default")
      (node (ref "U3") (pin "11") (pinfunction "INT2_11") (pintype "unspecified"))
    )
    (net (code "140") (name "unconnected-(U3-INTM-Pad13)") (class "Default")
      (node (ref "U3") (pin "13") (pinfunction "INTM_13") (pintype "unspecified"))
    )
    (net (code "141") (name "unconnected-(U3-SDOAG-Pad8)") (class "Default")
      (node (ref "U3") (pin "8") (pinfunction "SDOAG_8") (pintype "unspecified"))
    )
    (net (code "142") (name "unconnected-(U6-3V3-Pad2)") (class "Default")
      (node (ref "U6") (pin "2") (pinfunction "3V3_2") (pintype "passive"))
    )
    (net (code "143") (name "unconnected-(U6-CS-Pad7)") (class "Default")
      (node (ref "U6") (pin "7") (pinfunction "CS_7") (pintype "bidirectional"))
    )
    (net (code "144") (name "unconnected-(U6-INT-Pad8)") (class "Default")
      (node (ref "U6") (pin "8") (pinfunction "INT_8") (pintype "bidirectional"))
    )
    (net (code "145") (name "unconnected-(U6-SDO-Pad5)") (class "Default")
      (node (ref "U6") (pin "5") (pinfunction "SDO_5") (pintype "bidirectional"))
    )
    (net (code "146") (name "unconnected-(U7-3V3-Pad2)") (class "Default")
      (node (ref "U7") (pin "2") (pinfunction "3V3_2") (pintype "passive"))
    )
    (net (code "147") (name "unconnected-(U7-CS-Pad7)") (class "Default")
      (node (ref "U7") (pin "7") (pinfunction "CS_7") (pintype "bidirectional"))
    )
    (net (code "148") (name "unconnected-(U7-INT-Pad8)") (class "Default")
      (node (ref "U7") (pin "8") (pinfunction "INT_8") (pintype "bidirectional"))
    )
    (net (code "149") (name "unconnected-(U7-SDO-Pad5)") (class "Default")
      (node (ref "U7") (pin "5") (pinfunction "SDO_5") (pintype "bidirectional"))
    )
  )
)
